# DRC10_2P4X1P65_pac.net
KiCad netlist of a schematic drawn in EAGLE
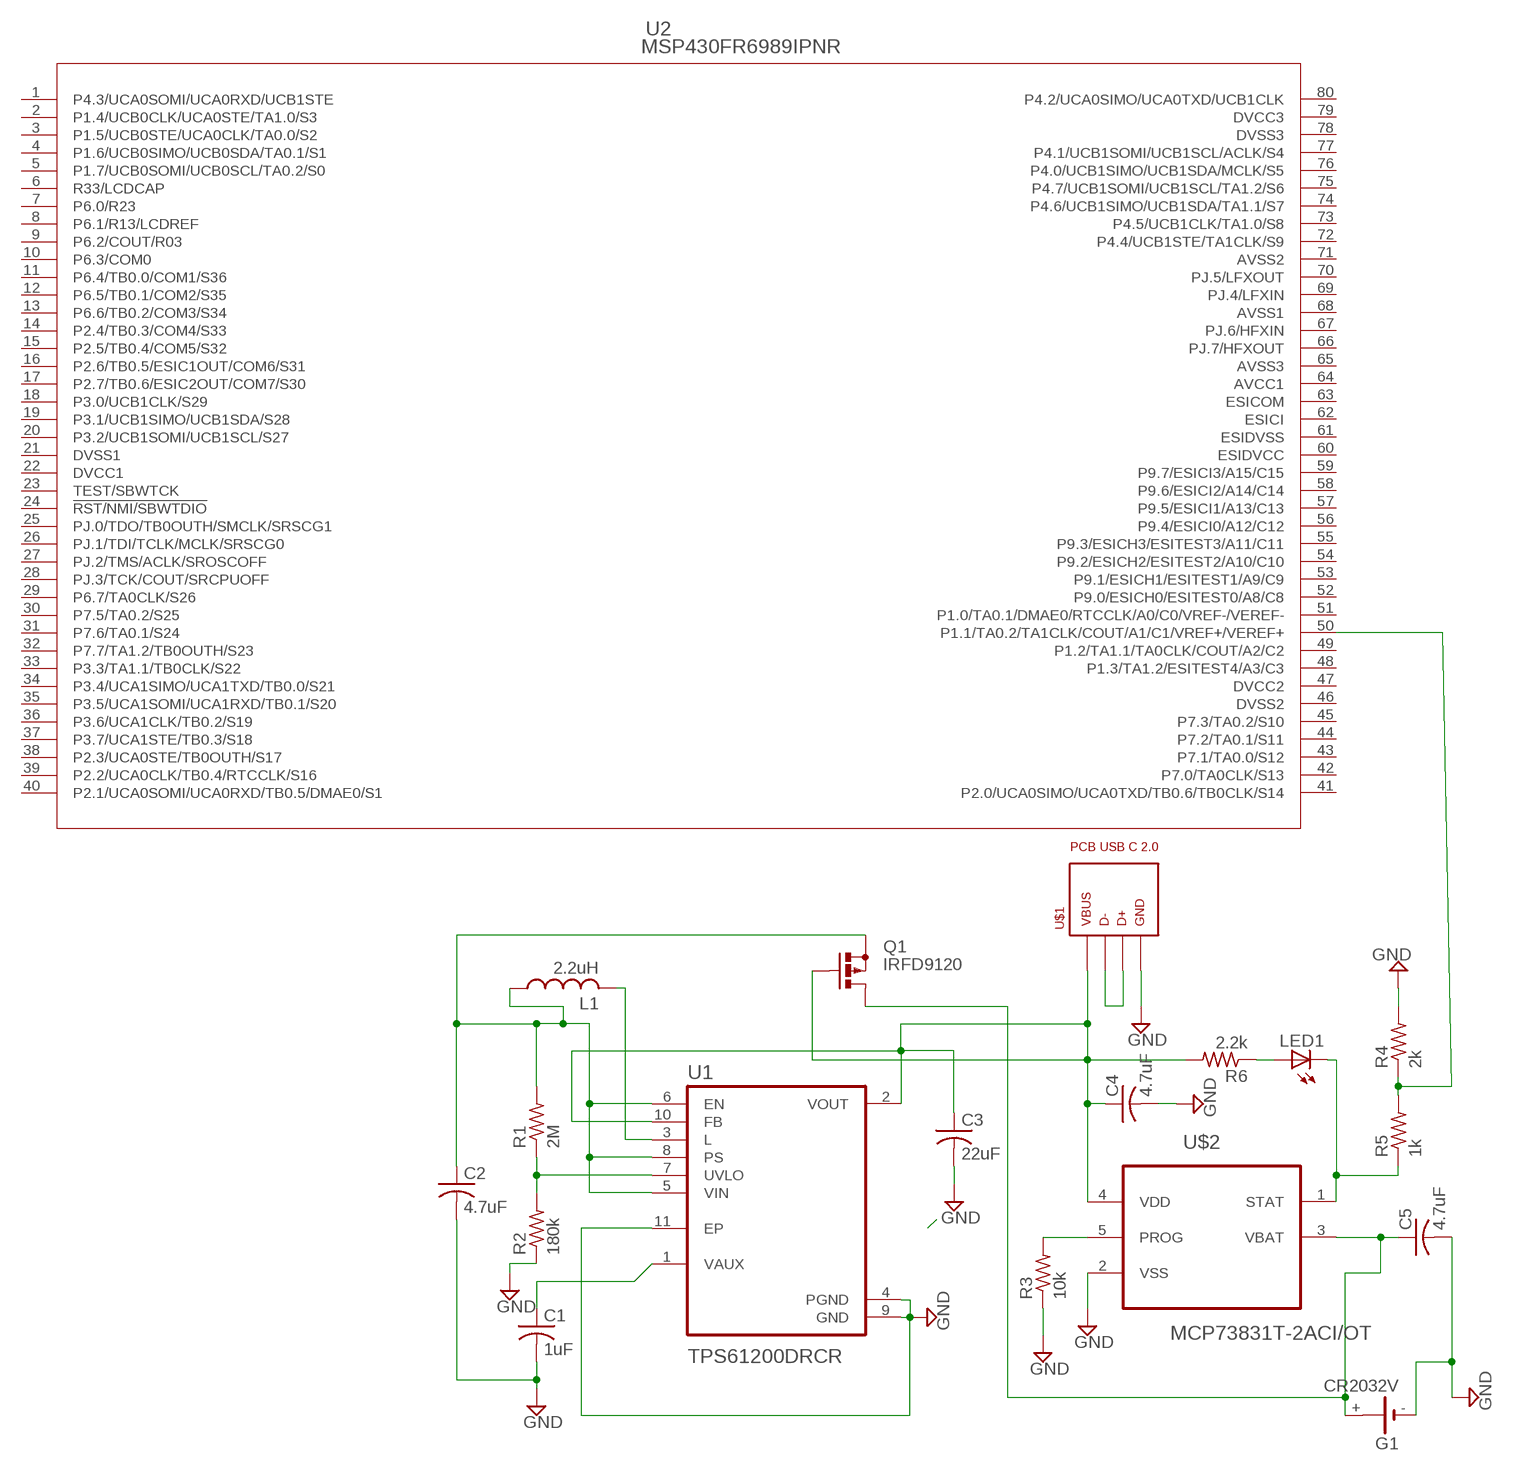
[diagram p0: schematic, sheet 1]

(export (version "E")
  (design (tool "Eeschema 10.0.6"))
  (components
    (comp (ref "C1")
      (value "1uF")
      (footprint "eagle-import:C150-072X183")
      (libsource (lib "eagle-import") (part "C-US150-072X183"))
    )
    (comp (ref "C2")
      (value "4.7uF")
      (footprint "eagle-import:C150-072X183")
      (libsource (lib "eagle-import") (part "C-US150-072X183"))
    )
    (comp (ref "C3")
      (value "22uF")
      (footprint "eagle-import:C150-072X183")
      (libsource (lib "eagle-import") (part "C-US150-072X183"))
    )
    (comp (ref "C4")
      (value "4.7uF")
      (footprint "eagle-import:C150-072X183")
      (libsource (lib "eagle-import") (part "C-US150-072X183"))
    )
    (comp (ref "C5")
      (value "4.7uF")
      (footprint "eagle-import:C150-072X183")
      (libsource (lib "eagle-import") (part "C-US150-072X183"))
    )
    (comp (ref "G1")
      (value "CR2032V")
      (footprint "eagle-import:CR2032V")
      (libsource (lib "eagle-import") (part "CR2032V"))
    )
    (comp (ref "L1")
      (value "2.2uH")
      (footprint "eagle-import:0207_15")
      (libsource (lib "eagle-import") (part "L-US0207/15"))
    )
    (comp (ref "LED1")
      (value "LEDB155")
      (footprint "eagle-import:Q62902-B155")
      (libsource (lib "eagle-import") (part "LEDB155"))
    )
    (comp (ref "Q1")
      (value "IRFD9120")
      (footprint "eagle-import:C370-01")
      (libsource (lib "eagle-import") (part "IRFD9120"))
    )
    (comp (ref "R1")
      (value "2M")
      (footprint "eagle-import:0414_15")
      (libsource (lib "eagle-import") (part "R-US_0414/15"))
    )
    (comp (ref "R2")
      (value "180k")
      (footprint "eagle-import:0414_15")
      (libsource (lib "eagle-import") (part "R-US_0414/15"))
    )
    (comp (ref "R3")
      (value "10k")
      (footprint "eagle-import:0414_15")
      (libsource (lib "eagle-import") (part "R-US_0414/15"))
    )
    (comp (ref "R4")
      (value "2k")
      (footprint "eagle-import:0414_15")
      (libsource (lib "eagle-import") (part "R-US_0414/15"))
    )
    (comp (ref "R5")
      (value "1k")
      (footprint "eagle-import:0414_15")
      (libsource (lib "eagle-import") (part "R-US_0414/15"))
    )
    (comp (ref "R6")
      (value "2.2k")
      (footprint "eagle-import:0414_15")
      (libsource (lib "eagle-import") (part "R-US_0414/15"))
    )
    (comp (ref "U$1")
      (value "PCB_USB_C_2.0DS_1")
      (footprint "eagle-import:USB_TYPE_C_DS_1")
      (libsource (lib "eagle-import") (part "PCB_USB_C_2.0DS_1"))
    )
    (comp (ref "U$2")
      (value "MCP73831T-2ACI/OT")
      (footprint "eagle-import:SOT95P280X145-5N")
      (fields (field (name "MF") "Microchip"))
      (libsource (lib "eagle-import") (part "MCP73831T-2ACI/OT"))
    )
    (comp (ref "U1")
      (value "TPS61200DRCR")
      (footprint "eagle-import:VREG_V62_16624-01YE")
      (fields (field (name "MF") "Texas Instruments"))
      (libsource (lib "eagle-import") (part "TPS61200DRCR"))
    )
    (comp (ref "U2")
      (value "MSP430FR6989IPNR")
      (footprint "eagle-import:PN80_TEX")
      (libsource (lib "eagle-import") (part "MSP430FR6989IPNR"))
    )
  )
  (nets
    (net (code "1") (name "/AVCC1") (class "Default")
      (node (ref "U2") (pin "64") (pinfunction "AVCC1_64") (pintype "power_in"))
    )
    (net (code "2") (name "/AVSS1") (class "Default")
      (node (ref "U2") (pin "68") (pinfunction "AVSS1_68") (pintype "power_in"))
    )
    (net (code "3") (name "/AVSS2") (class "Default")
      (node (ref "U2") (pin "71") (pinfunction "AVSS2_71") (pintype "power_in"))
    )
    (net (code "4") (name "/AVSS3") (class "Default")
      (node (ref "U2") (pin "65") (pinfunction "AVSS3_65") (pintype "power_in"))
    )
    (net (code "5") (name "/DVCC1") (class "Default")
      (node (ref "U2") (pin "22") (pinfunction "DVCC1_22") (pintype "power_in"))
    )
    (net (code "6") (name "/DVCC2") (class "Default")
      (node (ref "U2") (pin "47") (pinfunction "DVCC2_47") (pintype "power_in"))
    )
    (net (code "7") (name "/DVCC3") (class "Default")
      (node (ref "U2") (pin "79") (pinfunction "DVCC3_79") (pintype "power_in"))
    )
    (net (code "8") (name "/DVSS1") (class "Default")
      (node (ref "U2") (pin "21") (pinfunction "DVSS1_21") (pintype "power_in"))
    )
    (net (code "9") (name "/DVSS2") (class "Default")
      (node (ref "U2") (pin "46") (pinfunction "DVSS2_46") (pintype "power_in"))
    )
    (net (code "10") (name "/DVSS3") (class "Default")
      (node (ref "U2") (pin "78") (pinfunction "DVSS3_78") (pintype "power_in"))
    )
    (net (code "11") (name "/ESIDVCC") (class "Default")
      (node (ref "U2") (pin "60") (pinfunction "ESIDVCC_60") (pintype "power_in"))
    )
    (net (code "12") (name "/ESIDVSS") (class "Default")
      (node (ref "U2") (pin "61") (pinfunction "ESIDVSS_61") (pintype "power_in"))
    )
    (net (code "13") (name "GND") (class "Default")
      (node (ref "C1") (pin "2") (pinfunction "2_2") (pintype "passive"))
      (node (ref "C2") (pin "2") (pinfunction "2_2") (pintype "passive"))
      (node (ref "C3") (pin "2") (pinfunction "2_2") (pintype "passive"))
      (node (ref "C4") (pin "2") (pinfunction "2_2") (pintype "passive"))
      (node (ref "C5") (pin "2") (pinfunction "2_2") (pintype "passive"))
      (node (ref "G1") (pin "-") (pinfunction "-_-") (pintype "passive"))
      (node (ref "R2") (pin "1") (pinfunction "1_1") (pintype "passive"))
      (node (ref "R3") (pin "1") (pinfunction "1_1") (pintype "passive"))
      (node (ref "R4") (pin "2") (pinfunction "2_2") (pintype "passive"))
      (node (ref "U$1") (pin "A1") (pinfunction "GND_A1") (pintype "bidirectional"))
      (node (ref "U$1") (pin "A12") (pinfunction "GND_A12") (pintype "bidirectional"))
      (node (ref "U$1") (pin "B1") (pinfunction "GND_B1") (pintype "bidirectional"))
      (node (ref "U$1") (pin "B12") (pinfunction "GND_B12") (pintype "bidirectional"))
      (node (ref "U$2") (pin "2") (pinfunction "VSS_2") (pintype "power_in"))
      (node (ref "U1") (pin "11") (pinfunction "EP_11") (pintype "bidirectional"))
      (node (ref "U1") (pin "4") (pinfunction "PGND_4") (pintype "power_in"))
      (node (ref "U1") (pin "9") (pinfunction "GND_9") (pintype "power_in"))
    )
    (net (code "14") (name "Net-(LED1-C)") (class "Default")
      (node (ref "LED1") (pin "K") (pinfunction "C_K") (pintype "passive"))
      (node (ref "R5") (pin "1") (pinfunction "1_1") (pintype "passive"))
      (node (ref "U$2") (pin "1") (pinfunction "STAT_1") (pintype "output"))
    )
    (net (code "15") (name "Net-(LED1-PadA)") (class "Default")
      (node (ref "LED1") (pin "A") (pinfunction "A_A") (pintype "passive"))
      (node (ref "R6") (pin "1") (pinfunction "1_1") (pintype "passive"))
    )
    (net (code "16") (name "Net-(U$1-D+-PadA6)") (class "Default")
      (node (ref "U$1") (pin "A6") (pinfunction "D+_A6") (pintype "bidirectional"))
      (node (ref "U$1") (pin "A7") (pinfunction "D-_A7") (pintype "bidirectional"))
      (node (ref "U$1") (pin "B6") (pinfunction "D+_B6") (pintype "bidirectional"))
      (node (ref "U$1") (pin "B7") (pinfunction "D-_B7") (pintype "bidirectional"))
    )
    (net (code "17") (name "Net-(U$2-PROG)") (class "Default")
      (node (ref "R3") (pin "2") (pinfunction "2_2") (pintype "passive"))
      (node (ref "U$2") (pin "5") (pinfunction "PROG_5") (pintype "input"))
    )
    (net (code "18") (name "Net-(U$2-VBAT)") (class "Default")
      (node (ref "C5") (pin "1") (pinfunction "1_1") (pintype "passive"))
      (node (ref "G1") (pin "+") (pinfunction "+_+") (pintype "passive"))
      (node (ref "Q1") (pin "D") (pinfunction "D_D") (pintype "passive"))
      (node (ref "Q1") (pin "D1") (pinfunction "D_D1") (pintype "passive"))
      (node (ref "U$2") (pin "3") (pinfunction "VBAT_3") (pintype "output"))
    )
    (net (code "19") (name "Net-(U$2-VDD)") (class "Default")
      (node (ref "C3") (pin "1") (pinfunction "1_1") (pintype "passive"))
      (node (ref "C4") (pin "1") (pinfunction "1_1") (pintype "passive"))
      (node (ref "Q1") (pin "G") (pinfunction "G_G") (pintype "passive"))
      (node (ref "R6") (pin "2") (pinfunction "2_2") (pintype "passive"))
      (node (ref "U$1") (pin "A4") (pinfunction "VBUS_A4") (pintype "bidirectional"))
      (node (ref "U$1") (pin "A9") (pinfunction "VBUS_A9") (pintype "bidirectional"))
      (node (ref "U$1") (pin "B4") (pinfunction "VBUS_B4") (pintype "bidirectional"))
      (node (ref "U$1") (pin "B9") (pinfunction "VBUS_B9") (pintype "bidirectional"))
      (node (ref "U$2") (pin "4") (pinfunction "VDD_4") (pintype "power_in"))
      (node (ref "U1") (pin "10") (pinfunction "FB_10") (pintype "input"))
      (node (ref "U1") (pin "2") (pinfunction "VOUT_2") (pintype "output"))
    )
    (net (code "20") (name "Net-(U1-EN)") (class "Default")
      (node (ref "C2") (pin "1") (pinfunction "1_1") (pintype "passive"))
      (node (ref "L1") (pin "1") (pinfunction "1_1") (pintype "passive"))
      (node (ref "Q1") (pin "S") (pinfunction "S_S") (pintype "passive"))
      (node (ref "R1") (pin "2") (pinfunction "2_2") (pintype "passive"))
      (node (ref "U1") (pin "5") (pinfunction "VIN_5") (pintype "input"))
      (node (ref "U1") (pin "6") (pinfunction "EN_6") (pintype "input"))
      (node (ref "U1") (pin "8") (pinfunction "PS_8") (pintype "input"))
    )
    (net (code "21") (name "Net-(U1-L)") (class "Default")
      (node (ref "L1") (pin "2") (pinfunction "2_2") (pintype "passive"))
      (node (ref "U1") (pin "3") (pinfunction "L_3") (pintype "input"))
    )
    (net (code "22") (name "Net-(U1-UVLO)") (class "Default")
      (node (ref "R1") (pin "1") (pinfunction "1_1") (pintype "passive"))
      (node (ref "R2") (pin "2") (pinfunction "2_2") (pintype "passive"))
      (node (ref "U1") (pin "7") (pinfunction "UVLO_7") (pintype "input"))
    )
    (net (code "23") (name "Net-(U1-VAUX)") (class "Default")
      (node (ref "C1") (pin "1") (pinfunction "1_1") (pintype "passive"))
      (node (ref "U1") (pin "1") (pinfunction "VAUX_1") (pintype "bidirectional"))
    )
    (net (code "24") (name "Net-(U2-P1.1{slash}TA0.2{slash}TA1CLK{slash}COUT{slash}A1{slash}C1{slash}VREF+{slash}VEREF+)") (class "Default")
      (node (ref "R4") (pin "1") (pinfunction "1_1") (pintype "passive"))
      (node (ref "R5") (pin "2") (pinfunction "2_2") (pintype "passive"))
      (node (ref "U2") (pin "50") (pinfunction "P1.1/TA0.2/TA1CLK/COUT/A1/C1/VREF+/VEREF+_50") (pintype "bidirectional"))
    )
    (net (code "25") (name "unconnected-(G1-+-Pad+@1)") (class "Default")
      (node (ref "G1") (pin "+@1") (pinfunction "+_+@1") (pintype "passive"))
    )
    (net (code "26") (name "unconnected-(U2-ESICI-Pad62)") (class "Default")
      (node (ref "U2") (pin "62") (pinfunction "ESICI_62") (pintype "input"))
    )
    (net (code "27") (name "unconnected-(U2-ESICOM-Pad63)") (class "Default")
      (node (ref "U2") (pin "63") (pinfunction "ESICOM_63") (pintype "passive"))
    )
    (net (code "28") (name "unconnected-(U2-P1.0{slash}TA0.1{slash}DMAE0{slash}RTCCLK{slash}A0{slash}C0{slash}VREF-{slash}VEREF--Pad51)") (class "Default")
      (node (ref "U2") (pin "51") (pinfunction "P1.0/TA0.1/DMAE0/RTCCLK/A0/C0/VREF-/VEREF-_51") (pintype "bidirectional"))
    )
    (net (code "29") (name "unconnected-(U2-P1.2{slash}TA1.1{slash}TA0CLK{slash}COUT{slash}A2{slash}C2-Pad49)") (class "Default")
      (node (ref "U2") (pin "49") (pinfunction "P1.2/TA1.1/TA0CLK/COUT/A2/C2_49") (pintype "bidirectional"))
    )
    (net (code "30") (name "unconnected-(U2-P1.3{slash}TA1.2{slash}ESITEST4{slash}A3{slash}C3-Pad48)") (class "Default")
      (node (ref "U2") (pin "48") (pinfunction "P1.3/TA1.2/ESITEST4/A3/C3_48") (pintype "bidirectional"))
    )
    (net (code "31") (name "unconnected-(U2-P1.4{slash}UCB0CLK{slash}UCA0STE{slash}TA1.0{slash}S3-Pad2)") (class "Default")
      (node (ref "U2") (pin "2") (pinfunction "P1.4/UCB0CLK/UCA0STE/TA1.0/S3_2") (pintype "bidirectional"))
    )
    (net (code "32") (name "unconnected-(U2-P1.5{slash}UCB0STE{slash}UCA0CLK{slash}TA0.0{slash}S2-Pad3)") (class "Default")
      (node (ref "U2") (pin "3") (pinfunction "P1.5/UCB0STE/UCA0CLK/TA0.0/S2_3") (pintype "bidirectional"))
    )
    (net (code "33") (name "unconnected-(U2-P1.6{slash}UCB0SIMO{slash}UCB0SDA{slash}TA0.1{slash}S1-Pad4)") (class "Default")
      (node (ref "U2") (pin "4") (pinfunction "P1.6/UCB0SIMO/UCB0SDA/TA0.1/S1_4") (pintype "bidirectional"))
    )
    (net (code "34") (name "unconnected-(U2-P1.7{slash}UCB0SOMI{slash}UCB0SCL{slash}TA0.2{slash}S0-Pad5)") (class "Default")
      (node (ref "U2") (pin "5") (pinfunction "P1.7/UCB0SOMI/UCB0SCL/TA0.2/S0_5") (pintype "bidirectional"))
    )
    (net (code "35") (name "unconnected-(U2-P2.0{slash}UCA0SIMO{slash}UCA0TXD{slash}TB0.6{slash}TB0CLK{slash}S14-Pad41)") (class "Default")
      (node (ref "U2") (pin "41") (pinfunction "P2.0/UCA0SIMO/UCA0TXD/TB0.6/TB0CLK/S14_41") (pintype "bidirectional"))
    )
    (net (code "36") (name "unconnected-(U2-P2.1{slash}UCA0SOMI{slash}UCA0RXD{slash}TB0.5{slash}DMAE0{slash}S1-Pad40)") (class "Default")
      (node (ref "U2") (pin "40") (pinfunction "P2.1/UCA0SOMI/UCA0RXD/TB0.5/DMAE0/S1_40") (pintype "bidirectional"))
    )
    (net (code "37") (name "unconnected-(U2-P2.2{slash}UCA0CLK{slash}TB0.4{slash}RTCCLK{slash}S16-Pad39)") (class "Default")
      (node (ref "U2") (pin "39") (pinfunction "P2.2/UCA0CLK/TB0.4/RTCCLK/S16_39") (pintype "bidirectional"))
    )
    (net (code "38") (name "unconnected-(U2-P2.3{slash}UCA0STE{slash}TB0OUTH{slash}S17-Pad38)") (class "Default")
      (node (ref "U2") (pin "38") (pinfunction "P2.3/UCA0STE/TB0OUTH/S17_38") (pintype "bidirectional"))
    )
    (net (code "39") (name "unconnected-(U2-P2.4{slash}TB0.3{slash}COM4{slash}S33-Pad14)") (class "Default")
      (node (ref "U2") (pin "14") (pinfunction "P2.4/TB0.3/COM4/S33_14") (pintype "bidirectional"))
    )
    (net (code "40") (name "unconnected-(U2-P2.5{slash}TB0.4{slash}COM5{slash}S32-Pad15)") (class "Default")
      (node (ref "U2") (pin "15") (pinfunction "P2.5/TB0.4/COM5/S32_15") (pintype "bidirectional"))
    )
    (net (code "41") (name "unconnected-(U2-P2.6{slash}TB0.5{slash}ESIC1OUT{slash}COM6{slash}S31-Pad16)") (class "Default")
      (node (ref "U2") (pin "16") (pinfunction "P2.6/TB0.5/ESIC1OUT/COM6/S31_16") (pintype "bidirectional"))
    )
    (net (code "42") (name "unconnected-(U2-P2.7{slash}TB0.6{slash}ESIC2OUT{slash}COM7{slash}S30-Pad17)") (class "Default")
      (node (ref "U2") (pin "17") (pinfunction "P2.7/TB0.6/ESIC2OUT/COM7/S30_17") (pintype "bidirectional"))
    )
    (net (code "43") (name "unconnected-(U2-P3.0{slash}UCB1CLK{slash}S29-Pad18)") (class "Default")
      (node (ref "U2") (pin "18") (pinfunction "P3.0/UCB1CLK/S29_18") (pintype "bidirectional"))
    )
    (net (code "44") (name "unconnected-(U2-P3.1{slash}UCB1SIMO{slash}UCB1SDA{slash}S28-Pad19)") (class "Default")
      (node (ref "U2") (pin "19") (pinfunction "P3.1/UCB1SIMO/UCB1SDA/S28_19") (pintype "bidirectional"))
    )
    (net (code "45") (name "unconnected-(U2-P3.2{slash}UCB1SOMI{slash}UCB1SCL{slash}S27-Pad20)") (class "Default")
      (node (ref "U2") (pin "20") (pinfunction "P3.2/UCB1SOMI/UCB1SCL/S27_20") (pintype "bidirectional"))
    )
    (net (code "46") (name "unconnected-(U2-P3.3{slash}TA1.1{slash}TB0CLK{slash}S22-Pad33)") (class "Default")
      (node (ref "U2") (pin "33") (pinfunction "P3.3/TA1.1/TB0CLK/S22_33") (pintype "bidirectional"))
    )
    (net (code "47") (name "unconnected-(U2-P3.4{slash}UCA1SIMO{slash}UCA1TXD{slash}TB0.0{slash}S21-Pad34)") (class "Default")
      (node (ref "U2") (pin "34") (pinfunction "P3.4/UCA1SIMO/UCA1TXD/TB0.0/S21_34") (pintype "bidirectional"))
    )
    (net (code "48") (name "unconnected-(U2-P3.5{slash}UCA1SOMI{slash}UCA1RXD{slash}TB0.1{slash}S20-Pad35)") (class "Default")
      (node (ref "U2") (pin "35") (pinfunction "P3.5/UCA1SOMI/UCA1RXD/TB0.1/S20_35") (pintype "bidirectional"))
    )
    (net (code "49") (name "unconnected-(U2-P3.6{slash}UCA1CLK{slash}TB0.2{slash}S19-Pad36)") (class "Default")
      (node (ref "U2") (pin "36") (pinfunction "P3.6/UCA1CLK/TB0.2/S19_36") (pintype "bidirectional"))
    )
    (net (code "50") (name "unconnected-(U2-P3.7{slash}UCA1STE{slash}TB0.3{slash}S18-Pad37)") (class "Default")
      (node (ref "U2") (pin "37") (pinfunction "P3.7/UCA1STE/TB0.3/S18_37") (pintype "bidirectional"))
    )
    (net (code "51") (name "unconnected-(U2-P4.0{slash}UCB1SIMO{slash}UCB1SDA{slash}MCLK{slash}S5-Pad76)") (class "Default")
      (node (ref "U2") (pin "76") (pinfunction "P4.0/UCB1SIMO/UCB1SDA/MCLK/S5_76") (pintype "bidirectional"))
    )
    (net (code "52") (name "unconnected-(U2-P4.1{slash}UCB1SOMI{slash}UCB1SCL{slash}ACLK{slash}S4-Pad77)") (class "Default")
      (node (ref "U2") (pin "77") (pinfunction "P4.1/UCB1SOMI/UCB1SCL/ACLK/S4_77") (pintype "bidirectional"))
    )
    (net (code "53") (name "unconnected-(U2-P4.2{slash}UCA0SIMO{slash}UCA0TXD{slash}UCB1CLK-Pad80)") (class "Default")
      (node (ref "U2") (pin "80") (pinfunction "P4.2/UCA0SIMO/UCA0TXD/UCB1CLK_80") (pintype "bidirectional"))
    )
    (net (code "54") (name "unconnected-(U2-P4.3{slash}UCA0SOMI{slash}UCA0RXD{slash}UCB1STE-Pad1)") (class "Default")
      (node (ref "U2") (pin "1") (pinfunction "P4.3/UCA0SOMI/UCA0RXD/UCB1STE_1") (pintype "bidirectional"))
    )
    (net (code "55") (name "unconnected-(U2-P4.4{slash}UCB1STE{slash}TA1CLK{slash}S9-Pad72)") (class "Default")
      (node (ref "U2") (pin "72") (pinfunction "P4.4/UCB1STE/TA1CLK/S9_72") (pintype "bidirectional"))
    )
    (net (code "56") (name "unconnected-(U2-P4.5{slash}UCB1CLK{slash}TA1.0{slash}S8-Pad73)") (class "Default")
      (node (ref "U2") (pin "73") (pinfunction "P4.5/UCB1CLK/TA1.0/S8_73") (pintype "bidirectional"))
    )
    (net (code "57") (name "unconnected-(U2-P4.6{slash}UCB1SIMO{slash}UCB1SDA{slash}TA1.1{slash}S7-Pad74)") (class "Default")
      (node (ref "U2") (pin "74") (pinfunction "P4.6/UCB1SIMO/UCB1SDA/TA1.1/S7_74") (pintype "bidirectional"))
    )
    (net (code "58") (name "unconnected-(U2-P4.7{slash}UCB1SOMI{slash}UCB1SCL{slash}TA1.2{slash}S6-Pad75)") (class "Default")
      (node (ref "U2") (pin "75") (pinfunction "P4.7/UCB1SOMI/UCB1SCL/TA1.2/S6_75") (pintype "bidirectional"))
    )
    (net (code "59") (name "unconnected-(U2-P6.0{slash}R23-Pad7)") (class "Default")
      (node (ref "U2") (pin "7") (pinfunction "P6.0/R23_7") (pintype "bidirectional"))
    )
    (net (code "60") (name "unconnected-(U2-P6.1{slash}R13{slash}LCDREF-Pad8)") (class "Default")
      (node (ref "U2") (pin "8") (pinfunction "P6.1/R13/LCDREF_8") (pintype "bidirectional"))
    )
    (net (code "61") (name "unconnected-(U2-P6.2{slash}COUT{slash}R03-Pad9)") (class "Default")
      (node (ref "U2") (pin "9") (pinfunction "P6.2/COUT/R03_9") (pintype "bidirectional"))
    )
    (net (code "62") (name "unconnected-(U2-P6.3{slash}COM0-Pad10)") (class "Default")
      (node (ref "U2") (pin "10") (pinfunction "P6.3/COM0_10") (pintype "bidirectional"))
    )
    (net (code "63") (name "unconnected-(U2-P6.4{slash}TB0.0{slash}COM1{slash}S36-Pad11)") (class "Default")
      (node (ref "U2") (pin "11") (pinfunction "P6.4/TB0.0/COM1/S36_11") (pintype "bidirectional"))
    )
    (net (code "64") (name "unconnected-(U2-P6.5{slash}TB0.1{slash}COM2{slash}S35-Pad12)") (class "Default")
      (node (ref "U2") (pin "12") (pinfunction "P6.5/TB0.1/COM2/S35_12") (pintype "bidirectional"))
    )
    (net (code "65") (name "unconnected-(U2-P6.6{slash}TB0.2{slash}COM3{slash}S34-Pad13)") (class "Default")
      (node (ref "U2") (pin "13") (pinfunction "P6.6/TB0.2/COM3/S34_13") (pintype "bidirectional"))
    )
    (net (code "66") (name "unconnected-(U2-P6.7{slash}TA0CLK{slash}S26-Pad29)") (class "Default")
      (node (ref "U2") (pin "29") (pinfunction "P6.7/TA0CLK/S26_29") (pintype "bidirectional"))
    )
    (net (code "67") (name "unconnected-(U2-P7.0{slash}TA0CLK{slash}S13-Pad42)") (class "Default")
      (node (ref "U2") (pin "42") (pinfunction "P7.0/TA0CLK/S13_42") (pintype "bidirectional"))
    )
    (net (code "68") (name "unconnected-(U2-P7.1{slash}TA0.0{slash}S12-Pad43)") (class "Default")
      (node (ref "U2") (pin "43") (pinfunction "P7.1/TA0.0/S12_43") (pintype "bidirectional"))
    )
    (net (code "69") (name "unconnected-(U2-P7.2{slash}TA0.1{slash}S11-Pad44)") (class "Default")
      (node (ref "U2") (pin "44") (pinfunction "P7.2/TA0.1/S11_44") (pintype "bidirectional"))
    )
    (net (code "70") (name "unconnected-(U2-P7.3{slash}TA0.2{slash}S10-Pad45)") (class "Default")
      (node (ref "U2") (pin "45") (pinfunction "P7.3/TA0.2/S10_45") (pintype "bidirectional"))
    )
    (net (code "71") (name "unconnected-(U2-P7.5{slash}TA0.2{slash}S25-Pad30)") (class "Default")
      (node (ref "U2") (pin "30") (pinfunction "P7.5/TA0.2/S25_30") (pintype "bidirectional"))
    )
    (net (code "72") (name "unconnected-(U2-P7.6{slash}TA0.1{slash}S24-Pad31)") (class "Default")
      (node (ref "U2") (pin "31") (pinfunction "P7.6/TA0.1/S24_31") (pintype "bidirectional"))
    )
    (net (code "73") (name "unconnected-(U2-P7.7{slash}TA1.2{slash}TB0OUTH{slash}S23-Pad32)") (class "Default")
      (node (ref "U2") (pin "32") (pinfunction "P7.7/TA1.2/TB0OUTH/S23_32") (pintype "bidirectional"))
    )
    (net (code "74") (name "unconnected-(U2-P9.0{slash}ESICH0{slash}ESITEST0{slash}A8{slash}C8-Pad52)") (class "Default")
      (node (ref "U2") (pin "52") (pinfunction "P9.0/ESICH0/ESITEST0/A8/C8_52") (pintype "bidirectional"))
    )
    (net (code "75") (name "unconnected-(U2-P9.1{slash}ESICH1{slash}ESITEST1{slash}A9{slash}C9-Pad53)") (class "Default")
      (node (ref "U2") (pin "53") (pinfunction "P9.1/ESICH1/ESITEST1/A9/C9_53") (pintype "bidirectional"))
    )
    (net (code "76") (name "unconnected-(U2-P9.2{slash}ESICH2{slash}ESITEST2{slash}A10{slash}C10-Pad54)") (class "Default")
      (node (ref "U2") (pin "54") (pinfunction "P9.2/ESICH2/ESITEST2/A10/C10_54") (pintype "bidirectional"))
    )
    (net (code "77") (name "unconnected-(U2-P9.3{slash}ESICH3{slash}ESITEST3{slash}A11{slash}C11-Pad55)") (class "Default")
      (node (ref "U2") (pin "55") (pinfunction "P9.3/ESICH3/ESITEST3/A11/C11_55") (pintype "bidirectional"))
    )
    (net (code "78") (name "unconnected-(U2-P9.4{slash}ESICI0{slash}A12{slash}C12-Pad56)") (class "Default")
      (node (ref "U2") (pin "56") (pinfunction "P9.4/ESICI0/A12/C12_56") (pintype "bidirectional"))
    )
    (net (code "79") (name "unconnected-(U2-P9.5{slash}ESICI1{slash}A13{slash}C13-Pad57)") (class "Default")
      (node (ref "U2") (pin "57") (pinfunction "P9.5/ESICI1/A13/C13_57") (pintype "bidirectional"))
    )
    (net (code "80") (name "unconnected-(U2-P9.6{slash}ESICI2{slash}A14{slash}C14-Pad58)") (class "Default")
      (node (ref "U2") (pin "58") (pinfunction "P9.6/ESICI2/A14/C14_58") (pintype "bidirectional"))
    )
    (net (code "81") (name "unconnected-(U2-P9.7{slash}ESICI3{slash}A15{slash}C15-Pad59)") (class "Default")
      (node (ref "U2") (pin "59") (pinfunction "P9.7/ESICI3/A15/C15_59") (pintype "bidirectional"))
    )
    (net (code "82") (name "unconnected-(U2-PJ.0{slash}TDO{slash}TB0OUTH{slash}SMCLK{slash}SRSCG1-Pad25)") (class "Default")
      (node (ref "U2") (pin "25") (pinfunction "PJ.0/TDO/TB0OUTH/SMCLK/SRSCG1_25") (pintype "bidirectional"))
    )
    (net (code "83") (name "unconnected-(U2-PJ.1{slash}TDI{slash}TCLK{slash}MCLK{slash}SRSCG0-Pad26)") (class "Default")
      (node (ref "U2") (pin "26") (pinfunction "PJ.1/TDI/TCLK/MCLK/SRSCG0_26") (pintype "bidirectional"))
    )
    (net (code "84") (name "unconnected-(U2-PJ.2{slash}TMS{slash}ACLK{slash}SROSCOFF-Pad27)") (class "Default")
      (node (ref "U2") (pin "27") (pinfunction "PJ.2/TMS/ACLK/SROSCOFF_27") (pintype "bidirectional"))
    )
    (net (code "85") (name "unconnected-(U2-PJ.3{slash}TCK{slash}COUT{slash}SRCPUOFF-Pad28)") (class "Default")
      (node (ref "U2") (pin "28") (pinfunction "PJ.3/TCK/COUT/SRCPUOFF_28") (pintype "bidirectional"))
    )
    (net (code "86") (name "unconnected-(U2-PJ.4{slash}LFXIN-Pad69)") (class "Default")
      (node (ref "U2") (pin "69") (pinfunction "PJ.4/LFXIN_69") (pintype "bidirectional"))
    )
    (net (code "87") (name "unconnected-(U2-PJ.5{slash}LFXOUT-Pad70)") (class "Default")
      (node (ref "U2") (pin "70") (pinfunction "PJ.5/LFXOUT_70") (pintype "bidirectional"))
    )
    (net (code "88") (name "unconnected-(U2-PJ.6{slash}HFXIN-Pad67)") (class "Default")
      (node (ref "U2") (pin "67") (pinfunction "PJ.6/HFXIN_67") (pintype "bidirectional"))
    )
    (net (code "89") (name "unconnected-(U2-PJ.7{slash}HFXOUT-Pad66)") (class "Default")
      (node (ref "U2") (pin "66") (pinfunction "PJ.7/HFXOUT_66") (pintype "bidirectional"))
    )
    (net (code "90") (name "unconnected-(U2-R33{slash}LCDCAP-Pad6)") (class "Default")
      (node (ref "U2") (pin "6") (pinfunction "R33/LCDCAP_6") (pintype "bidirectional"))
    )
    (net (code "91") (name "unconnected-(U2-TEST{slash}SBWTCK-Pad23)") (class "Default")
      (node (ref "U2") (pin "23") (pinfunction "TEST/SBWTCK_23") (pintype "input"))
    )
    (net (code "92") (name "unconnected-(U2-~{RST{slash}NMI{slash}SBWTDIO}-Pad24)") (class "Default")
      (node (ref "U2") (pin "24") (pinfunction "~{RST/NMI/SBWTDIO}_24") (pintype "bidirectional"))
    )
  )
)
